# Sheet1.net
KiCad netlist of a schematic drawn in Altium Designer
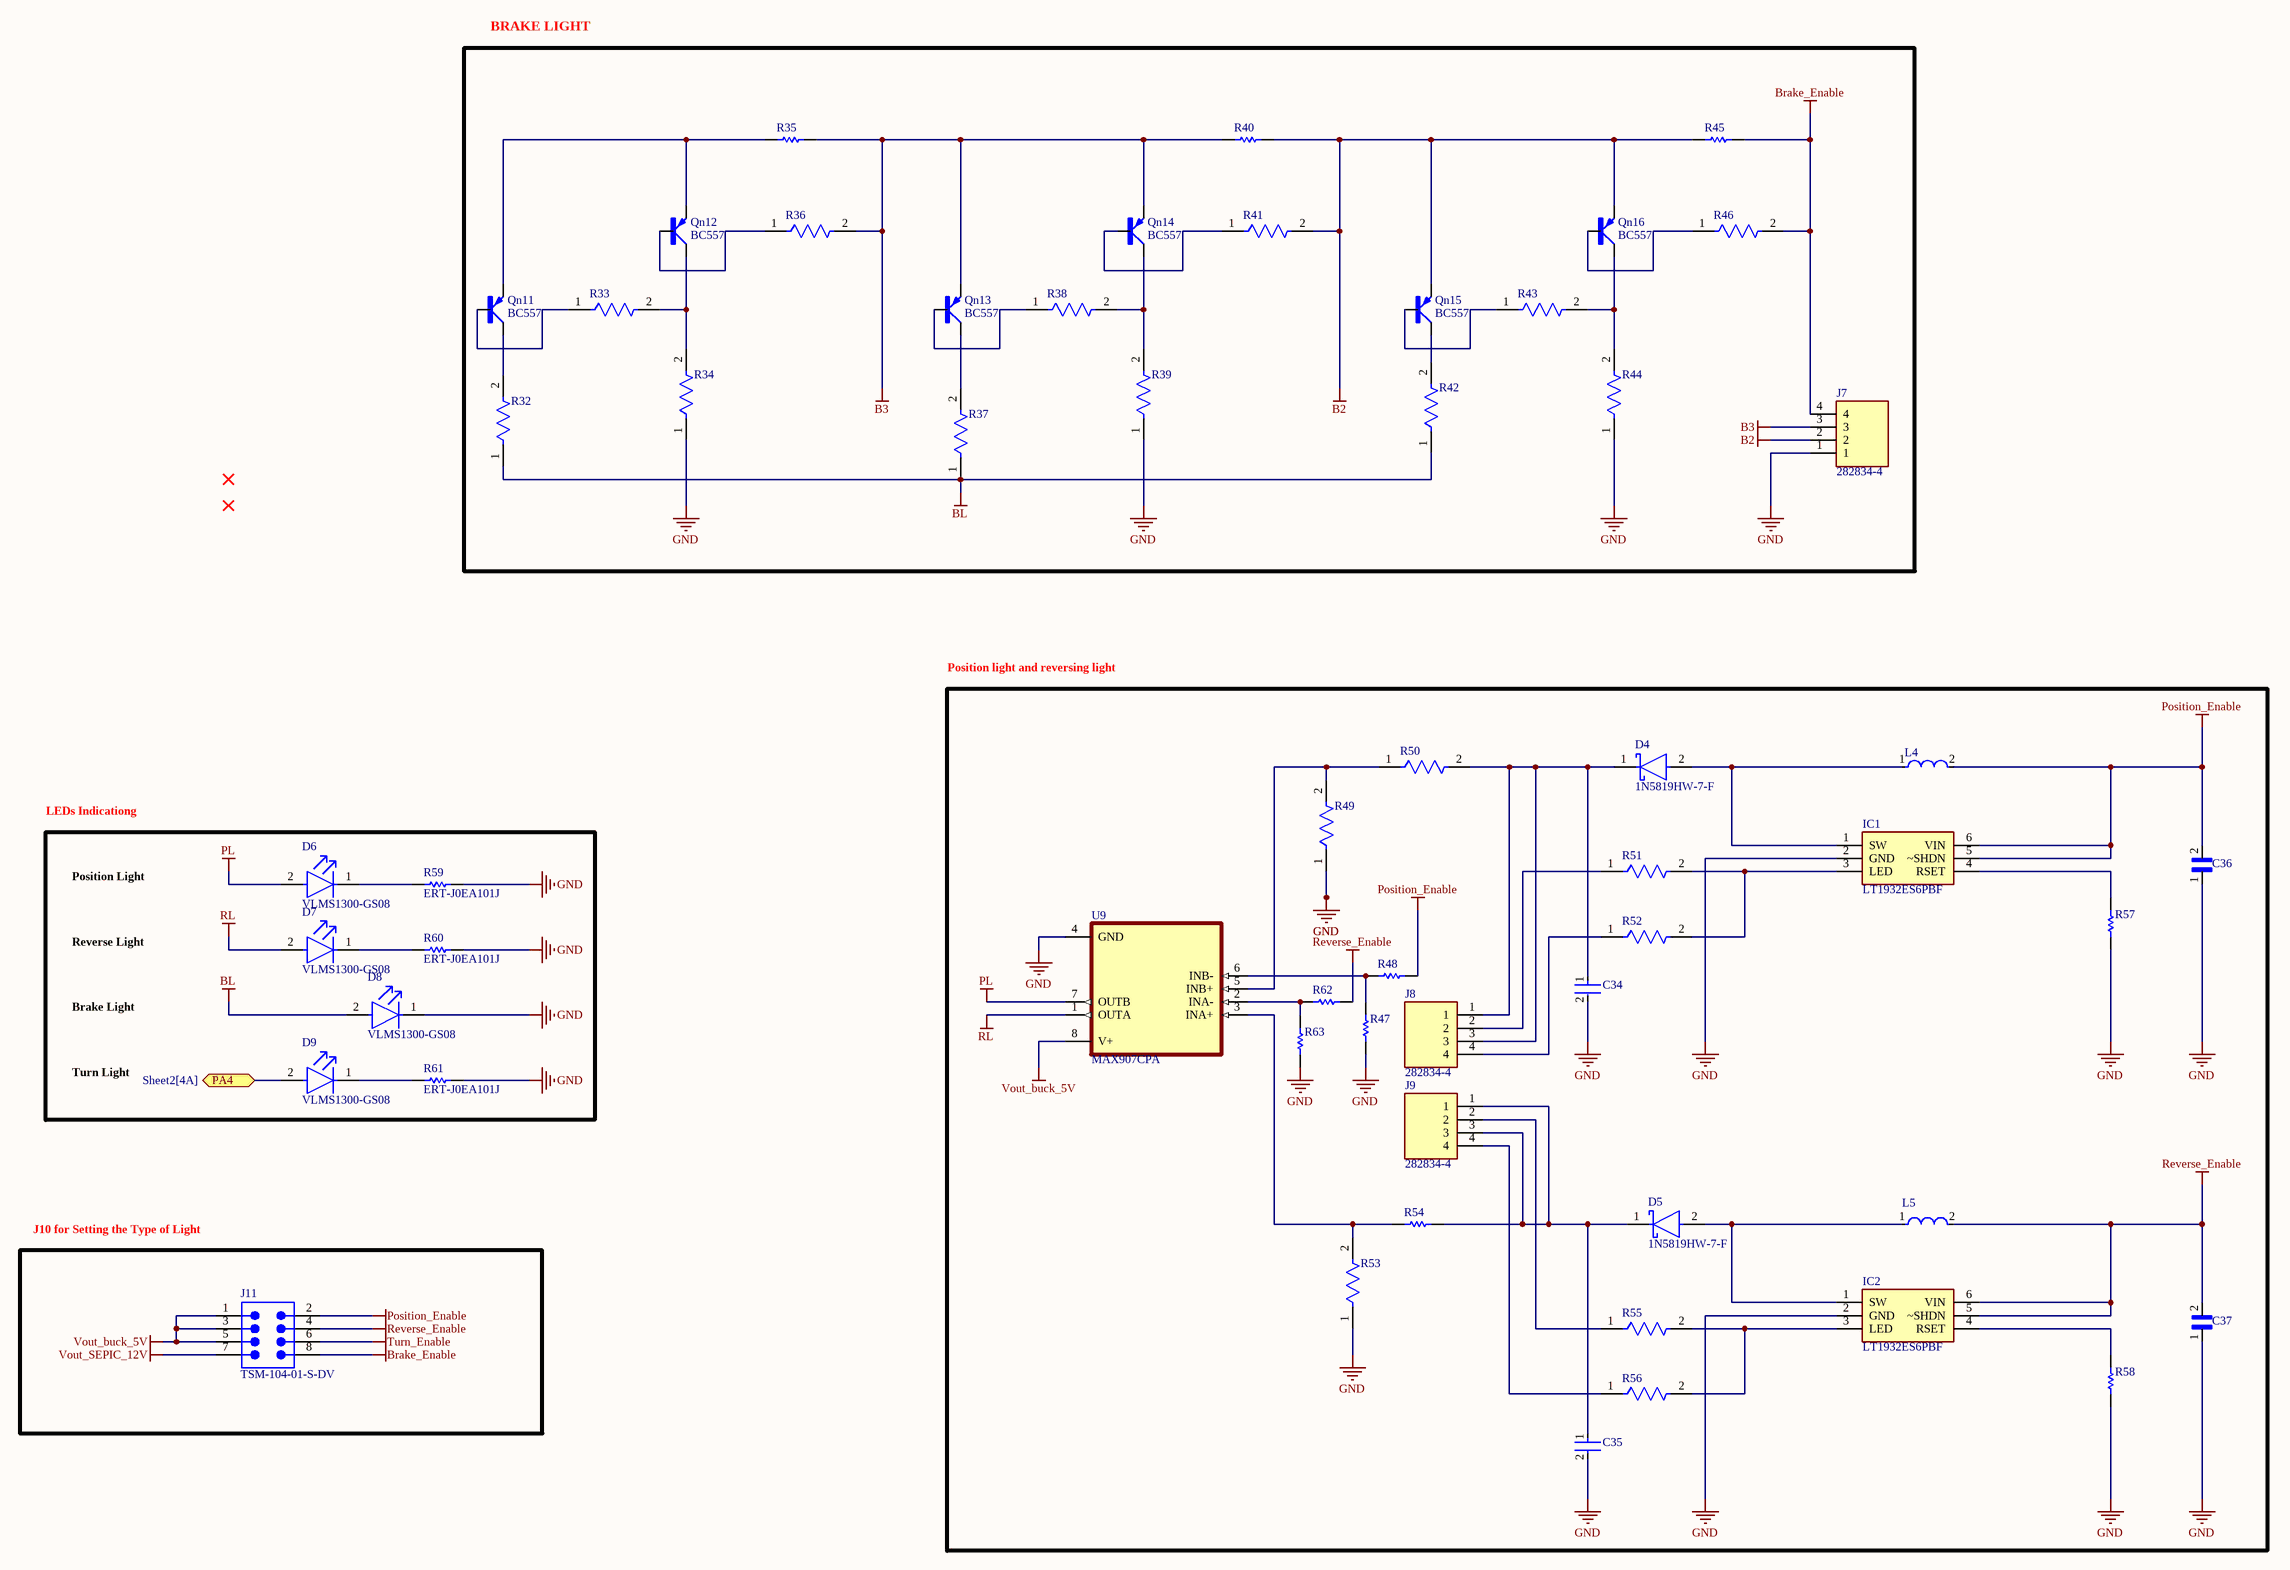
[diagram p0: Sheet1.SchDoc]

(export (version "E")
  (design (tool "Eeschema 10.0.6"))
  (components
    (comp (ref "C34")
      (value "TMK325BJ475KN-T")
      (footprint "FP-1210-L_3_2_0_3-W_2_5_0-IPC_C")
      (description "None")
      (fields (field (name "TOLERANCE") "10%"))
      (libsource (lib "Altium Content Vault") (part "02cd4be3c70576c341d710602a673aa"))
    )
    (comp (ref "C35")
      (value "TMK325BJ475KN-T")
      (footprint "FP-1210-L_3_2_0_3-W_2_5_0-IPC_C")
      (description "None")
      (fields (field (name "TOLERANCE") "10%"))
      (libsource (lib "Altium Content Vault") (part "02cd4be3c70576c341d710602a673aa"))
    )
    (comp (ref "C36")
      (value "JMK212BJ475MD-T")
      (footprint "CAPC2012X95N")
      (description "Cap Ceramic 4.7uF 6.3V X5R 20% Pad SMD 0805 85C T/R")
      (libsource (lib "JMK212BJ475MD-T") (part "JMK212BJ475MD-T"))
    )
    (comp (ref "C37")
      (value "JMK212BJ475MD-T")
      (footprint "CAPC2012X95N")
      (description "Cap Ceramic 4.7uF 6.3V X5R 20% Pad SMD 0805 85C T/R")
      (libsource (lib "JMK212BJ475MD-T") (part "JMK212BJ475MD-T"))
    )
    (comp (ref "D4")
      (value "1N5819HW-7-F")
      (footprint "FP-SOD123-IPC_A")
      (description "DIODE SCHOTTKY 40V 1A SOD123")
      (libsource (lib "Altium Content Vault") (part "1d6ec82d83fb6aee721767c19dac4b9"))
    )
    (comp (ref "D5")
      (value "1N5819HW-7-F")
      (footprint "FP-SOD123-IPC_A")
      (description "DIODE SCHOTTKY 40V 1A SOD123")
      (libsource (lib "Altium Content Vault") (part "1d6ec82d83fb6aee721767c19dac4b9"))
    )
    (comp (ref "D6")
      (value "VLMS1300-GS08")
      (footprint "FP-6_541-5092_01-4-MFG")
      (description "LED RED 0603 SMD")
      (fields
        (field (name "MANUFACTURER") "Vishay")
        (field (name "OCTOPART") "https://octopart.com/vlms1300-gs08-vishay-21709201")
      )
      (libsource (lib "Altium Content Vault") (part "8706943c75ba83719d021d2fdc84c58"))
    )
    (comp (ref "D7")
      (value "VLMS1300-GS08")
      (footprint "FP-6_541-5092_01-4-MFG")
      (description "LED RED 0603 SMD")
      (fields
        (field (name "MANUFACTURER") "Vishay")
        (field (name "OCTOPART") "https://octopart.com/vlms1300-gs08-vishay-21709201")
      )
      (libsource (lib "Altium Content Vault") (part "8706943c75ba83719d021d2fdc84c58"))
    )
    (comp (ref "D8")
      (value "VLMS1300-GS08")
      (footprint "FP-6_541-5092_01-4-MFG")
      (description "LED RED 0603 SMD")
      (fields
        (field (name "MANUFACTURER") "Vishay")
        (field (name "OCTOPART") "https://octopart.com/vlms1300-gs08-vishay-21709201")
      )
      (libsource (lib "Altium Content Vault") (part "8706943c75ba83719d021d2fdc84c58"))
    )
    (comp (ref "D9")
      (value "VLMS1300-GS08")
      (footprint "FP-6_541-5092_01-4-MFG")
      (description "LED RED 0603 SMD")
      (fields
        (field (name "MANUFACTURER") "Vishay")
        (field (name "OCTOPART") "https://octopart.com/vlms1300-gs08-vishay-21709201")
      )
      (libsource (lib "Altium Content Vault") (part "8706943c75ba83719d021d2fdc84c58"))
    )
    (comp (ref "IC1")
      (value "LT1932ES6PBF")
      (footprint "SamacSys:SOT95P280X145-6N")
      (description "Integrated Circuit")
      (libsource (lib "*") (part "LT1932ES6PBF"))
    )
    (comp (ref "IC2")
      (value "LT1932ES6PBF")
      (footprint "SamacSys:SOT95P280X145-6N")
      (description "Integrated Circuit")
      (libsource (lib "*") (part "LT1932ES6PBF"))
    )
    (comp (ref "J7")
      (value "282834-4")
      (footprint "TE_282834-4")
      (description "4 Position Wire to Board Terminal Block Horizontal with Board 0.100 (2.54mm) Through Hole")
      (fields (field (name "MF") "TE Connectivity"))
      (libsource (lib "282834-4") (part "282834-4"))
    )
    (comp (ref "J8")
      (value "282834-4")
      (footprint "TE_282834-4")
      (description "4 Position Wire to Board Terminal Block Horizontal with Board 0.100 (2.54mm) Through Hole")
      (fields (field (name "MF") "TE Connectivity"))
      (libsource (lib "") (part "282834-4_1"))
    )
    (comp (ref "J9")
      (value "282834-4")
      (footprint "TE_282834-4")
      (description "4 Position Wire to Board Terminal Block Horizontal with Board 0.100 (2.54mm) Through Hole")
      (fields (field (name "MF") "TE Connectivity"))
      (libsource (lib "") (part "282834-4_1"))
    )
    (comp (ref "J11")
      (value "TSM-104-01-S-DV")
      (footprint "SMTC-TSM-104-01-X-DV")
      (description "0.025\" SQ Post Header, Surface Mount, Vertical, -55 to 125 degC, 2.54 mm Pitch, 8-Pin, Male, RoHS")
      (fields (field (name "MANUFACTURER") "Samtec"))
      (libsource (lib "Altium Content Vault") (part "SMTC-TSM-104-01-X-X"))
    )
    (comp (ref "L4")
      (value "NRH3012T100MN")
      (footprint "FP-NR3012-MFG")
      (description "SMD Power Inductors 10uH ±20% 0.72A 0.27Ω")
      (fields (field (name "TOLERANCE") "20%"))
      (libsource (lib "Altium Content Vault") (part "725321dda6339637d4d059423bc1c3c"))
    )
    (comp (ref "L5")
      (value "NRH3012T100MN")
      (footprint "FP-NR3012-MFG")
      (description "SMD Power Inductors 10uH ±20% 0.72A 0.27Ω")
      (fields (field (name "TOLERANCE") "20%"))
      (libsource (lib "Altium Content Vault") (part "725321dda6339637d4d059423bc1c3c"))
    )
    (comp (ref "Qn11")
      (value "BC557")
      (footprint "SOT54A")
      (description "Bipolar (BJT) Transistor PNP 45 V 100 mA 320MHz 625 mW Through Hole TO-92 (TO-226)")
      (fields (field (name "MF") "ON"))
      (libsource (lib "BC557") (part "BC557"))
    )
    (comp (ref "Qn12")
      (value "BC557")
      (footprint "SOT54A")
      (description "Bipolar (BJT) Transistor PNP 45 V 100 mA 320MHz 625 mW Through Hole TO-92 (TO-226)")
      (fields (field (name "MF") "ON"))
      (libsource (lib "BC557") (part "BC557"))
    )
    (comp (ref "Qn13")
      (value "BC557")
      (footprint "SOT54A")
      (description "Bipolar (BJT) Transistor PNP 45 V 100 mA 320MHz 625 mW Through Hole TO-92 (TO-226)")
      (fields (field (name "MF") "ON"))
      (libsource (lib "BC557") (part "BC557"))
    )
    (comp (ref "Qn14")
      (value "BC557")
      (footprint "SOT54A")
      (description "Bipolar (BJT) Transistor PNP 45 V 100 mA 320MHz 625 mW Through Hole TO-92 (TO-226)")
      (fields (field (name "MF") "ON"))
      (libsource (lib "BC557") (part "BC557"))
    )
    (comp (ref "Qn15")
      (value "BC557")
      (footprint "SOT54A")
      (description "Bipolar (BJT) Transistor PNP 45 V 100 mA 320MHz 625 mW Through Hole TO-92 (TO-226)")
      (fields (field (name "MF") "ON"))
      (libsource (lib "BC557") (part "BC557"))
    )
    (comp (ref "Qn16")
      (value "BC557")
      (footprint "SOT54A")
      (description "Bipolar (BJT) Transistor PNP 45 V 100 mA 320MHz 625 mW Through Hole TO-92 (TO-226)")
      (fields (field (name "MF") "ON"))
      (libsource (lib "BC557") (part "BC557"))
    )
    (comp (ref "R32")
      (value "CRCW04021K00FKED")
      (footprint "FP-CRCW0402-e3-MFG")
      (description "RES Thick Film, 1kΩ, 1%, 0.063W, 100ppm/°C, 0402")
      (fields (field (name "TOLERANCE") "1%"))
      (libsource (lib "Altium Content Vault") (part "1029c3af85768c4190bb7ad29bc67b5"))
    )
    (comp (ref "R33")
      (value "CRCW04021K00FKED")
      (footprint "FP-CRCW0402-e3-MFG")
      (description "RES Thick Film, 1kΩ, 1%, 0.063W, 100ppm/°C, 0402")
      (fields (field (name "TOLERANCE") "1%"))
      (libsource (lib "Altium Content Vault") (part "1029c3af85768c4190bb7ad29bc67b5"))
    )
    (comp (ref "R34")
      (value "CRCW040210K0JNED")
      (footprint "FP-CRCW0402-e3-IPC_B")
      (description "RES Thick Film, 10kΩ, 5%, 0.063W, 200ppm/°C, 0402")
      (fields (field (name "TOLERANCE") "5%"))
      (libsource (lib "Altium Content Vault") (part "1029c3af85768c4190bb7ad29bc67b5"))
    )
    (comp (ref "R35")
      (value "CRCW0402240RFKED")
      (footprint "RESC1005X40X25ML05T05")
      (fields (field (name "MANUFACTURER") "Vishay Dale"))
      (libsource (lib "Altium Content Vault") (part "RES"))
    )
    (comp (ref "R36")
      (value "CRCW04021K00FKED")
      (footprint "FP-CRCW0402-e3-MFG")
      (description "RES Thick Film, 1kΩ, 1%, 0.063W, 100ppm/°C, 0402")
      (fields (field (name "TOLERANCE") "1%"))
      (libsource (lib "Altium Content Vault") (part "1029c3af85768c4190bb7ad29bc67b5"))
    )
    (comp (ref "R37")
      (value "CRCW04021K00FKED")
      (footprint "FP-CRCW0402-e3-MFG")
      (description "RES Thick Film, 1kΩ, 1%, 0.063W, 100ppm/°C, 0402")
      (fields (field (name "TOLERANCE") "1%"))
      (libsource (lib "Altium Content Vault") (part "1029c3af85768c4190bb7ad29bc67b5"))
    )
    (comp (ref "R38")
      (value "CRCW04021K00FKED")
      (footprint "FP-CRCW0402-e3-MFG")
      (description "RES Thick Film, 1kΩ, 1%, 0.063W, 100ppm/°C, 0402")
      (fields (field (name "TOLERANCE") "1%"))
      (libsource (lib "Altium Content Vault") (part "1029c3af85768c4190bb7ad29bc67b5"))
    )
    (comp (ref "R39")
      (value "CRCW040210K0JNED")
      (footprint "FP-CRCW0402-e3-IPC_B")
      (description "RES Thick Film, 10kΩ, 5%, 0.063W, 200ppm/°C, 0402")
      (fields (field (name "TOLERANCE") "5%"))
      (libsource (lib "Altium Content Vault") (part "1029c3af85768c4190bb7ad29bc67b5"))
    )
    (comp (ref "R40")
      (value "CRCW0402240RFKED")
      (footprint "RESC1005X40X25ML05T05")
      (fields (field (name "MANUFACTURER") "Vishay Dale"))
      (libsource (lib "Altium Content Vault") (part "RES"))
    )
    (comp (ref "R41")
      (value "CRCW04021K00FKED")
      (footprint "FP-CRCW0402-e3-MFG")
      (description "RES Thick Film, 1kΩ, 1%, 0.063W, 100ppm/°C, 0402")
      (fields (field (name "TOLERANCE") "1%"))
      (libsource (lib "Altium Content Vault") (part "1029c3af85768c4190bb7ad29bc67b5"))
    )
    (comp (ref "R42")
      (value "CRCW04021K00FKED")
      (footprint "FP-CRCW0402-e3-MFG")
      (description "RES Thick Film, 1kΩ, 1%, 0.063W, 100ppm/°C, 0402")
      (fields (field (name "TOLERANCE") "1%"))
      (libsource (lib "Altium Content Vault") (part "1029c3af85768c4190bb7ad29bc67b5"))
    )
    (comp (ref "R43")
      (value "CRCW04021K00FKED")
      (footprint "FP-CRCW0402-e3-MFG")
      (description "RES Thick Film, 1kΩ, 1%, 0.063W, 100ppm/°C, 0402")
      (fields (field (name "TOLERANCE") "1%"))
      (libsource (lib "Altium Content Vault") (part "1029c3af85768c4190bb7ad29bc67b5"))
    )
    (comp (ref "R44")
      (value "CRCW040210K0JNED")
      (footprint "FP-CRCW0402-e3-IPC_B")
      (description "RES Thick Film, 10kΩ, 5%, 0.063W, 200ppm/°C, 0402")
      (fields (field (name "TOLERANCE") "5%"))
      (libsource (lib "Altium Content Vault") (part "1029c3af85768c4190bb7ad29bc67b5"))
    )
    (comp (ref "R45")
      (value "CRCW0402240RFKED")
      (footprint "RESC1005X40X25ML05T05")
      (fields (field (name "MANUFACTURER") "Vishay Dale"))
      (libsource (lib "Altium Content Vault") (part "RES"))
    )
    (comp (ref "R46")
      (value "CRCW04021K00FKED")
      (footprint "FP-CRCW0402-e3-MFG")
      (description "RES Thick Film, 1kΩ, 1%, 0.063W, 100ppm/°C, 0402")
      (fields (field (name "TOLERANCE") "1%"))
      (libsource (lib "Altium Content Vault") (part "1029c3af85768c4190bb7ad29bc67b5"))
    )
    (comp (ref "R47")
      (value "ERJ-3EKF1001V")
      (footprint "RESC1608X55X30LL15T15")
      (fields (field (name "MANUFACTURER") "Panasonic"))
      (libsource (lib "Altium Content Vault") (part "RES"))
    )
    (comp (ref "R48")
      (value "CPF0402B665RE1")
      (footprint "RESC1005X35X20ML05T10")
      (fields (field (name "MANUFACTURER") "TE Connectivity / AMP"))
      (libsource (lib "Altium Content Vault") (part "RES"))
    )
    (comp (ref "R49")
      (value "RC0603FR-071KL")
      (footprint "FP-RC0603-0_55-IPC_C")
      (description "RES 1K OHM 1% 1/10W 0603")
      (fields (field (name "TOLERANCE") "1%"))
      (libsource (lib "Altium Content Vault") (part "1029c3af85768c4190bb7ad29bc67b5"))
    )
    (comp (ref "R50")
      (value "RC3216J432CS")
      (footprint "FP-RC3216-IPC_B")
      (description "Res Thick Film 1206 4.3kΩ 5% 0.25W ±100ppm/°C Molded SMD T/R")
      (fields (field (name "TOLERANCE") "5%"))
      (libsource (lib "Altium Content Vault") (part "1029c3af85768c4190bb7ad29bc67b5"))
    )
    (comp (ref "R51")
      (value "CRCW0402100RJNED")
      (footprint "FP-CRCW0402-e3-IPC_A")
      (description "RES Thick Film, 100Ω, 5%, 0.063W, 200ppm/°C, 0402")
      (fields (field (name "TOLERANCE") "5%"))
      (libsource (lib "Altium Content Vault") (part "1029c3af85768c4190bb7ad29bc67b5"))
    )
    (comp (ref "R52")
      (value "CRCW0402100RJNED")
      (footprint "FP-CRCW0402-e3-IPC_A")
      (description "RES Thick Film, 100Ω, 5%, 0.063W, 200ppm/°C, 0402")
      (fields (field (name "TOLERANCE") "5%"))
      (libsource (lib "Altium Content Vault") (part "1029c3af85768c4190bb7ad29bc67b5"))
    )
    (comp (ref "R53")
      (value "RC0603FR-071KL")
      (footprint "FP-RC0603-0_55-IPC_C")
      (description "RES 1K OHM 1% 1/10W 0603")
      (fields (field (name "TOLERANCE") "1%"))
      (libsource (lib "Altium Content Vault") (part "1029c3af85768c4190bb7ad29bc67b5"))
    )
    (comp (ref "R54")
      (value "RC1206FR-072K2L")
      (footprint "RESC3116X65X40ML10T20")
      (description "Chip Resistor, 2.2 KOhm, +/- 1%, 250 mW, -55 to 155 degC, 1206 (3216 Metric), RoHS, Tape and Reel")
      (fields (field (name "MANUFACTURER") "Yageo") (field (name "TOLERANCE") "1%"))
      (libsource (lib "Altium Content Vault") (part "RES-2"))
    )
    (comp (ref "R55")
      (value "CRCW0402100RJNED")
      (footprint "FP-CRCW0402-e3-IPC_A")
      (description "RES Thick Film, 100Ω, 5%, 0.063W, 200ppm/°C, 0402")
      (fields (field (name "TOLERANCE") "5%"))
      (libsource (lib "Altium Content Vault") (part "1029c3af85768c4190bb7ad29bc67b5"))
    )
    (comp (ref "R56")
      (value "CRCW0402100RJNED")
      (footprint "FP-CRCW0402-e3-IPC_A")
      (description "RES Thick Film, 100Ω, 5%, 0.063W, 200ppm/°C, 0402")
      (fields (field (name "TOLERANCE") "5%"))
      (libsource (lib "Altium Content Vault") (part "1029c3af85768c4190bb7ad29bc67b5"))
    )
    (comp (ref "R57")
      (value "ERJ-2RKF5620X")
      (footprint "RESC1005X40X25LL05T05")
      (fields (field (name "MANUFACTURER") "Panasonic"))
      (libsource (lib "Altium Content Vault") (part "RES"))
    )
    (comp (ref "R58")
      (value "ERJ-2RKF5620X")
      (footprint "RESC1005X40X25LL05T05")
      (fields (field (name "MANUFACTURER") "Panasonic"))
      (libsource (lib "Altium Content Vault") (part "RES"))
    )
    (comp (ref "R59")
      (value "ERT-J0EA101J")
      (footprint "RESC1005X40X25NL05T05")
      (fields (field (name "MANUFACTURER") "Panasonic"))
      (libsource (lib "Altium Content Vault") (part "RES"))
    )
    (comp (ref "R60")
      (value "ERT-J0EA101J")
      (footprint "RESC1005X40X25NL05T05")
      (fields (field (name "MANUFACTURER") "Panasonic"))
      (libsource (lib "Altium Content Vault") (part "RES"))
    )
    (comp (ref "R61")
      (value "ERT-J0EA101J")
      (footprint "RESC1005X40X25NL05T05")
      (fields (field (name "MANUFACTURER") "Panasonic"))
      (libsource (lib "Altium Content Vault") (part "RES"))
    )
    (comp (ref "R62")
      (value "CPF0402B665RE1")
      (footprint "RESC1005X35X20ML05T10")
      (fields (field (name "MANUFACTURER") "TE Connectivity / AMP"))
      (libsource (lib "Altium Content Vault") (part "RES"))
    )
    (comp (ref "R63")
      (value "ERJ-3EKF1001V")
      (footprint "RESC1608X55X30LL15T15")
      (fields (field (name "MANUFACTURER") "Panasonic"))
      (libsource (lib "Altium Content Vault") (part "RES"))
    )
    (comp (ref "U9")
      (value "MAX907CPA")
      (footprint "DIP794W47P254L991H457Q8")
      (description "Comparator General Purpose TTL 8-PDIP")
      (fields (field (name "MF") "Maxim Integrated"))
      (libsource (lib "MAX907CPA") (part "MAX907CPA"))
    )
  )
  (nets
    (net (code "1") (name "/PA4") (class "Default")
      (node (ref "D9") (pin "2") (pinfunction "A_2") (pintype "passive"))
    )
    (net (code "2") (name "B2") (class "Default")
      (node (ref "J7") (pin "2") (pinfunction "2_2") (pintype "passive"))
      (node (ref "Qn15") (pin "E") (pinfunction "E_E") (pintype "passive"))
      (node (ref "Qn16") (pin "E") (pinfunction "E_E") (pintype "passive"))
      (node (ref "R40") (pin "2") (pinfunction "2_2") (pintype "passive"))
      (node (ref "R41") (pin "2") (pinfunction "2_2") (pintype "passive"))
      (node (ref "R45") (pin "1") (pinfunction "1_1") (pintype "passive"))
    )
    (net (code "3") (name "B3") (class "Default")
      (node (ref "J7") (pin "3") (pinfunction "3_3") (pintype "passive"))
      (node (ref "Qn13") (pin "E") (pinfunction "E_E") (pintype "passive"))
      (node (ref "Qn14") (pin "E") (pinfunction "E_E") (pintype "passive"))
      (node (ref "R35") (pin "2") (pinfunction "2_2") (pintype "passive"))
      (node (ref "R36") (pin "2") (pinfunction "2_2") (pintype "passive"))
      (node (ref "R40") (pin "1") (pinfunction "1_1") (pintype "passive"))
    )
    (net (code "4") (name "BL") (class "Default")
      (node (ref "D8") (pin "2") (pinfunction "A_2") (pintype "passive"))
      (node (ref "R32") (pin "1") (pinfunction "1_1") (pintype "passive"))
      (node (ref "R37") (pin "1") (pinfunction "1_1") (pintype "passive"))
      (node (ref "R42") (pin "1") (pinfunction "1_1") (pintype "passive"))
    )
    (net (code "5") (name "Brake_Enable") (class "Default")
      (node (ref "J11") (pin "8") (pinfunction "8_8") (pintype "passive"))
      (node (ref "J7") (pin "4") (pinfunction "4_4") (pintype "passive"))
      (node (ref "R45") (pin "2") (pinfunction "2_2") (pintype "passive"))
      (node (ref "R46") (pin "2") (pinfunction "2_2") (pintype "passive"))
    )
    (net (code "6") (name "GND") (class "Default")
      (node (ref "C34") (pin "2") (pinfunction "2_2") (pintype "passive"))
      (node (ref "C35") (pin "2") (pinfunction "2_2") (pintype "passive"))
      (node (ref "C36") (pin "1") (pinfunction "1_1") (pintype "passive"))
      (node (ref "C37") (pin "1") (pinfunction "1_1") (pintype "passive"))
      (node (ref "D8") (pin "1") (pinfunction "C_1") (pintype "passive"))
      (node (ref "IC1") (pin "2") (pinfunction "GND_2") (pintype "passive"))
      (node (ref "IC2") (pin "2") (pinfunction "GND_2") (pintype "passive"))
      (node (ref "J7") (pin "1") (pinfunction "1_1") (pintype "passive"))
      (node (ref "R34") (pin "1") (pinfunction "1_1") (pintype "passive"))
      (node (ref "R39") (pin "1") (pinfunction "1_1") (pintype "passive"))
      (node (ref "R44") (pin "1") (pinfunction "1_1") (pintype "passive"))
      (node (ref "R47") (pin "1") (pinfunction "1_1") (pintype "passive"))
      (node (ref "R49") (pin "1") (pinfunction "1_1") (pintype "passive"))
      (node (ref "R53") (pin "1") (pinfunction "1_1") (pintype "passive"))
      (node (ref "R57") (pin "1") (pinfunction "1_1") (pintype "passive"))
      (node (ref "R58") (pin "1") (pinfunction "1_1") (pintype "passive"))
      (node (ref "R59") (pin "2") (pinfunction "2_2") (pintype "passive"))
      (node (ref "R60") (pin "2") (pinfunction "2_2") (pintype "passive"))
      (node (ref "R61") (pin "2") (pinfunction "2_2") (pintype "passive"))
      (node (ref "R63") (pin "1") (pinfunction "1_1") (pintype "passive"))
      (node (ref "U9") (pin "4") (pinfunction "GND_4") (pintype "power_in"))
    )
    (net (code "7") (name "Net-(D4-A)") (class "Default")
      (node (ref "D4") (pin "2") (pinfunction "A_2") (pintype "passive"))
      (node (ref "IC1") (pin "1") (pinfunction "SW_1") (pintype "passive"))
      (node (ref "L4") (pin "1") (pinfunction "1_1") (pintype "passive"))
    )
    (net (code "8") (name "Net-(D4-C)") (class "Default")
      (node (ref "C34") (pin "1") (pinfunction "1_1") (pintype "passive"))
      (node (ref "D4") (pin "1") (pinfunction "C_1") (pintype "passive"))
      (node (ref "J8") (pin "1") (pinfunction "1_1") (pintype "passive"))
      (node (ref "J8") (pin "3") (pinfunction "3_3") (pintype "passive"))
      (node (ref "R50") (pin "2") (pinfunction "2_2") (pintype "passive"))
    )
    (net (code "9") (name "Net-(D5-A)") (class "Default")
      (node (ref "D5") (pin "2") (pinfunction "A_2") (pintype "passive"))
      (node (ref "IC2") (pin "1") (pinfunction "SW_1") (pintype "passive"))
      (node (ref "L5") (pin "1") (pinfunction "1_1") (pintype "passive"))
    )
    (net (code "10") (name "Net-(D5-C)") (class "Default")
      (node (ref "C35") (pin "1") (pinfunction "1_1") (pintype "passive"))
      (node (ref "D5") (pin "1") (pinfunction "C_1") (pintype "passive"))
      (node (ref "J9") (pin "1") (pinfunction "1_1") (pintype "passive"))
      (node (ref "J9") (pin "3") (pinfunction "3_3") (pintype "passive"))
      (node (ref "R54") (pin "2") (pinfunction "2_2") (pintype "passive"))
    )
    (net (code "11") (name "Net-(D6-C)") (class "Default")
      (node (ref "D6") (pin "1") (pinfunction "C_1") (pintype "passive"))
      (node (ref "R59") (pin "1") (pinfunction "1_1") (pintype "passive"))
    )
    (net (code "12") (name "Net-(D7-C)") (class "Default")
      (node (ref "D7") (pin "1") (pinfunction "C_1") (pintype "passive"))
      (node (ref "R60") (pin "1") (pinfunction "1_1") (pintype "passive"))
    )
    (net (code "13") (name "Net-(D9-C)") (class "Default")
      (node (ref "D9") (pin "1") (pinfunction "C_1") (pintype "passive"))
      (node (ref "R61") (pin "1") (pinfunction "1_1") (pintype "passive"))
    )
    (net (code "14") (name "Net-(IC1-LED)") (class "Default")
      (node (ref "IC1") (pin "3") (pinfunction "LED_3") (pintype "passive"))
      (node (ref "R51") (pin "2") (pinfunction "2_2") (pintype "passive"))
      (node (ref "R52") (pin "2") (pinfunction "2_2") (pintype "passive"))
    )
    (net (code "15") (name "Net-(IC1-RSET)") (class "Default")
      (node (ref "IC1") (pin "4") (pinfunction "RSET_4") (pintype "passive"))
      (node (ref "R57") (pin "2") (pinfunction "2_2") (pintype "passive"))
    )
    (net (code "16") (name "Net-(IC2-LED)") (class "Default")
      (node (ref "IC2") (pin "3") (pinfunction "LED_3") (pintype "passive"))
      (node (ref "R55") (pin "2") (pinfunction "2_2") (pintype "passive"))
      (node (ref "R56") (pin "2") (pinfunction "2_2") (pintype "passive"))
    )
    (net (code "17") (name "Net-(IC2-RSET)") (class "Default")
      (node (ref "IC2") (pin "4") (pinfunction "RSET_4") (pintype "passive"))
      (node (ref "R58") (pin "2") (pinfunction "2_2") (pintype "passive"))
    )
    (net (code "18") (name "Net-(J8-Pad2)") (class "Default")
      (node (ref "J8") (pin "2") (pinfunction "2_2") (pintype "passive"))
      (node (ref "R51") (pin "1") (pinfunction "1_1") (pintype "passive"))
    )
    (net (code "19") (name "Net-(J8-Pad4)") (class "Default")
      (node (ref "J8") (pin "4") (pinfunction "4_4") (pintype "passive"))
      (node (ref "R52") (pin "1") (pinfunction "1_1") (pintype "passive"))
    )
    (net (code "20") (name "Net-(J9-Pad2)") (class "Default")
      (node (ref "J9") (pin "2") (pinfunction "2_2") (pintype "passive"))
      (node (ref "R55") (pin "1") (pinfunction "1_1") (pintype "passive"))
    )
    (net (code "21") (name "Net-(J9-Pad4)") (class "Default")
      (node (ref "J9") (pin "4") (pinfunction "4_4") (pintype "passive"))
      (node (ref "R56") (pin "1") (pinfunction "1_1") (pintype "passive"))
    )
    (net (code "22") (name "Net-(Qn11-PadB)") (class "Default")
      (node (ref "Qn11") (pin "B") (pinfunction "B_B") (pintype "passive"))
      (node (ref "R33") (pin "1") (pinfunction "1_1") (pintype "passive"))
    )
    (net (code "23") (name "Net-(Qn11-PadC)") (class "Default")
      (node (ref "Qn11") (pin "C") (pinfunction "C_C") (pintype "passive"))
      (node (ref "R32") (pin "2") (pinfunction "2_2") (pintype "passive"))
    )
    (net (code "24") (name "Net-(Qn11-PadE)") (class "Default")
      (node (ref "Qn11") (pin "E") (pinfunction "E_E") (pintype "passive"))
      (node (ref "Qn12") (pin "E") (pinfunction "E_E") (pintype "passive"))
      (node (ref "R35") (pin "1") (pinfunction "1_1") (pintype "passive"))
    )
    (net (code "25") (name "Net-(Qn12-PadB)") (class "Default")
      (node (ref "Qn12") (pin "B") (pinfunction "B_B") (pintype "passive"))
      (node (ref "R36") (pin "1") (pinfunction "1_1") (pintype "passive"))
    )
    (net (code "26") (name "Net-(Qn12-PadC)") (class "Default")
      (node (ref "Qn12") (pin "C") (pinfunction "C_C") (pintype "passive"))
      (node (ref "R33") (pin "2") (pinfunction "2_2") (pintype "passive"))
      (node (ref "R34") (pin "2") (pinfunction "2_2") (pintype "passive"))
    )
    (net (code "27") (name "Net-(Qn13-PadB)") (class "Default")
      (node (ref "Qn13") (pin "B") (pinfunction "B_B") (pintype "passive"))
      (node (ref "R38") (pin "1") (pinfunction "1_1") (pintype "passive"))
    )
    (net (code "28") (name "Net-(Qn13-PadC)") (class "Default")
      (node (ref "Qn13") (pin "C") (pinfunction "C_C") (pintype "passive"))
      (node (ref "R37") (pin "2") (pinfunction "2_2") (pintype "passive"))
    )
    (net (code "29") (name "Net-(Qn14-PadB)") (class "Default")
      (node (ref "Qn14") (pin "B") (pinfunction "B_B") (pintype "passive"))
      (node (ref "R41") (pin "1") (pinfunction "1_1") (pintype "passive"))
    )
    (net (code "30") (name "Net-(Qn14-PadC)") (class "Default")
      (node (ref "Qn14") (pin "C") (pinfunction "C_C") (pintype "passive"))
      (node (ref "R38") (pin "2") (pinfunction "2_2") (pintype "passive"))
      (node (ref "R39") (pin "2") (pinfunction "2_2") (pintype "passive"))
    )
    (net (code "31") (name "Net-(Qn15-PadB)") (class "Default")
      (node (ref "Qn15") (pin "B") (pinfunction "B_B") (pintype "passive"))
      (node (ref "R43") (pin "1") (pinfunction "1_1") (pintype "passive"))
    )
    (net (code "32") (name "Net-(Qn15-PadC)") (class "Default")
      (node (ref "Qn15") (pin "C") (pinfunction "C_C") (pintype "passive"))
      (node (ref "R42") (pin "2") (pinfunction "2_2") (pintype "passive"))
    )
    (net (code "33") (name "Net-(Qn16-PadB)") (class "Default")
      (node (ref "Qn16") (pin "B") (pinfunction "B_B") (pintype "passive"))
      (node (ref "R46") (pin "1") (pinfunction "1_1") (pintype "passive"))
    )
    (net (code "34") (name "Net-(Qn16-PadC)") (class "Default")
      (node (ref "Qn16") (pin "C") (pinfunction "C_C") (pintype "passive"))
      (node (ref "R43") (pin "2") (pinfunction "2_2") (pintype "passive"))
      (node (ref "R44") (pin "2") (pinfunction "2_2") (pintype "passive"))
    )
    (net (code "35") (name "Net-(U9-INA+)") (class "Default")
      (node (ref "R53") (pin "2") (pinfunction "2_2") (pintype "passive"))
      (node (ref "R54") (pin "1") (pinfunction "1_1") (pintype "passive"))
      (node (ref "U9") (pin "3") (pinfunction "INA+_3") (pintype "input"))
    )
    (net (code "36") (name "Net-(U9-INA-)") (class "Default")
      (node (ref "R62") (pin "1") (pinfunction "1_1") (pintype "passive"))
      (node (ref "R63") (pin "2") (pinfunction "2_2") (pintype "passive"))
      (node (ref "U9") (pin "2") (pinfunction "INA-_2") (pintype "input"))
    )
    (net (code "37") (name "Net-(U9-INB+)") (class "Default")
      (node (ref "R49") (pin "2") (pinfunction "2_2") (pintype "passive"))
      (node (ref "R50") (pin "1") (pinfunction "1_1") (pintype "passive"))
      (node (ref "U9") (pin "5") (pinfunction "INB+_5") (pintype "input"))
    )
    (net (code "38") (name "Net-(U9-INB-)") (class "Default")
      (node (ref "R47") (pin "2") (pinfunction "2_2") (pintype "passive"))
      (node (ref "R48") (pin "1") (pinfunction "1_1") (pintype "passive"))
      (node (ref "U9") (pin "6") (pinfunction "INB-_6") (pintype "input"))
    )
    (net (code "39") (name "PL") (class "Default")
      (node (ref "D6") (pin "2") (pinfunction "A_2") (pintype "passive"))
      (node (ref "U9") (pin "7") (pinfunction "OUTB_7") (pintype "output"))
    )
    (net (code "40") (name "Position_Enable") (class "Default")
      (node (ref "C36") (pin "2") (pinfunction "2_2") (pintype "passive"))
      (node (ref "IC1") (pin "5") (pinfunction "~SHDN_5") (pintype "passive"))
      (node (ref "IC1") (pin "6") (pinfunction "VIN_6") (pintype "passive"))
      (node (ref "J11") (pin "2") (pinfunction "2_2") (pintype "passive"))
      (node (ref "L4") (pin "2") (pinfunction "2_2") (pintype "passive"))
      (node (ref "R48") (pin "2") (pinfunction "2_2") (pintype "passive"))
    )
    (net (code "41") (name "RL") (class "Default")
      (node (ref "D7") (pin "2") (pinfunction "A_2") (pintype "passive"))
      (node (ref "U9") (pin "1") (pinfunction "OUTA_1") (pintype "output"))
    )
    (net (code "42") (name "Reverse_Enable") (class "Default")
      (node (ref "C37") (pin "2") (pinfunction "2_2") (pintype "passive"))
      (node (ref "IC2") (pin "5") (pinfunction "~SHDN_5") (pintype "passive"))
      (node (ref "IC2") (pin "6") (pinfunction "VIN_6") (pintype "passive"))
      (node (ref "J11") (pin "4") (pinfunction "4_4") (pintype "passive"))
      (node (ref "L5") (pin "2") (pinfunction "2_2") (pintype "passive"))
      (node (ref "R62") (pin "2") (pinfunction "2_2") (pintype "passive"))
    )
    (net (code "43") (name "Turn_Enable") (class "Default")
      (node (ref "J11") (pin "6") (pinfunction "6_6") (pintype "passive"))
    )
    (net (code "44") (name "Vout_SEPIC_12V") (class "Default")
      (node (ref "J11") (pin "7") (pinfunction "7_7") (pintype "passive"))
    )
    (net (code "45") (name "Vout_buck_5V") (class "Default")
      (node (ref "J11") (pin "1") (pinfunction "1_1") (pintype "passive"))
      (node (ref "J11") (pin "3") (pinfunction "3_3") (pintype "passive"))
      (node (ref "J11") (pin "5") (pinfunction "5_5") (pintype "passive"))
      (node (ref "U9") (pin "8") (pinfunction "V+_8") (pintype "power_in"))
    )
  )
)
